# Main.net
KiCad netlist of a schematic drawn in Altium Designer
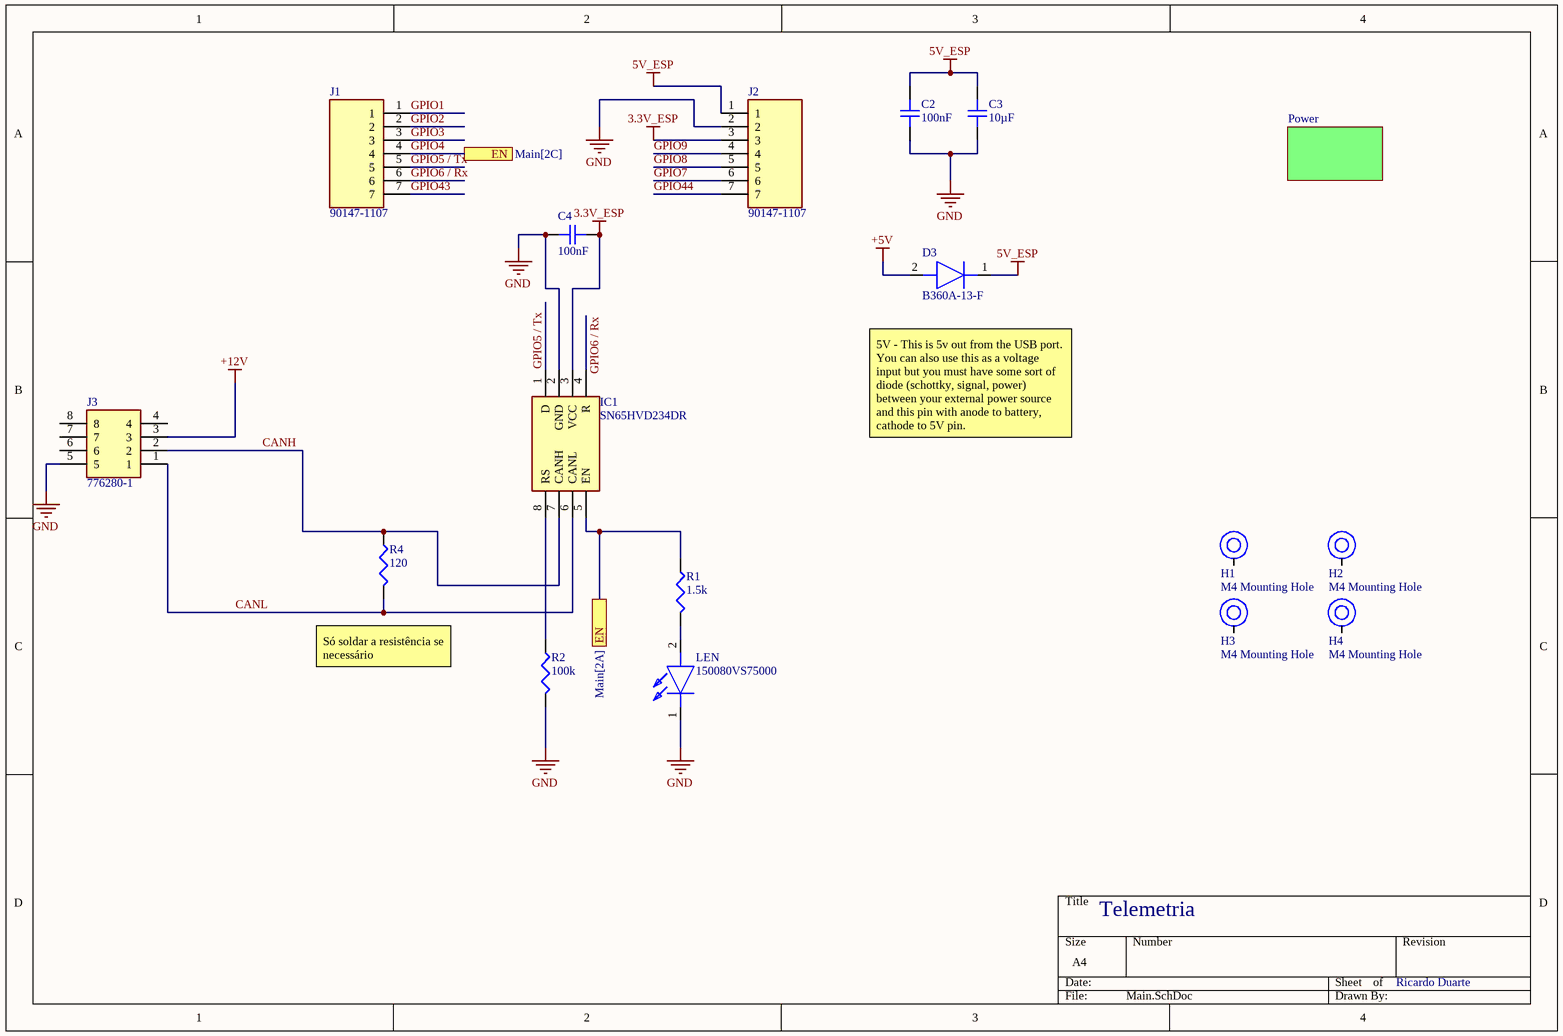
[diagram p0: Main.SchDoc]

(export (version "E")
  (design (tool "Eeschema 10.0.6"))
  (components
    (comp (ref "C2")
      (value "100nF")
      (footprint "CAP_0805")
      (fields (field (name "SOURCE") "Schematic-Lib-PhilsLab.SchLib"))
      (libsource (lib "EMEA- ISEL Formula Student-Instituto Superior Tecnico - Universidade de Lisboa") (part "100nF"))
    )
    (comp (ref "C3")
      (value "10µF")
      (footprint "CAP_0805")
      (fields (field (name "Comment") "10uF") (field (name "SOURCE") "Schematic-Lib-PhilsLab.SchLib"))
      (libsource (lib "EMEA- ISEL Formula Student-Instituto Superior Tecnico - Universidade de Lisboa") (part "10uF"))
    )
    (comp (ref "C4")
      (value "100nF")
      (footprint "CAP_0805")
      (fields (field (name "SOURCE") "Schematic-Lib-PhilsLab.SchLib"))
      (libsource (lib "EMEA- ISEL Formula Student-Instituto Superior Tecnico - Universidade de Lisboa") (part "100nF"))
    )
    (comp (ref "D3")
      (value "B360A-13-F")
      (footprint "FP-SMA-MFG")
      (description "Rectifier Diode, Schottky, 1 Phase, 1 Element, 3A, 60V V(RRM), Silicon")
      (fields (field (name "MOUSER PART NUMBER") "621-B360A-F"))
      (libsource (lib "EMEA- ISEL Formula Student-Instituto Superior Tecnico - Universidade de Lisboa") (part "B360A-13-F"))
    )
    (comp (ref "H1")
      (value "M4 Mounting Hole")
      (footprint "M4 Screw Hole-Footprint-1")
      (description "IFS Standard M4 hole for mounting PCBs")
      (libsource (lib "EMEA- ISEL Formula Student-Instituto Superior Tecnico - Universidade de Lisboa") (part "M4 Mounting  Hole"))
    )
    (comp (ref "H2")
      (value "M4 Mounting Hole")
      (footprint "M4 Screw Hole-Footprint-1")
      (description "IFS Standard M4 hole for mounting PCBs")
      (libsource (lib "EMEA- ISEL Formula Student-Instituto Superior Tecnico - Universidade de Lisboa") (part "M4 Mounting  Hole"))
    )
    (comp (ref "H3")
      (value "M4 Mounting Hole")
      (footprint "M4 Screw Hole-Footprint-1")
      (description "IFS Standard M4 hole for mounting PCBs")
      (libsource (lib "EMEA- ISEL Formula Student-Instituto Superior Tecnico - Universidade de Lisboa") (part "M4 Mounting  Hole"))
    )
    (comp (ref "H4")
      (value "M4 Mounting Hole")
      (footprint "M4 Screw Hole-Footprint-1")
      (description "IFS Standard M4 hole for mounting PCBs")
      (libsource (lib "EMEA- ISEL Formula Student-Instituto Superior Tecnico - Universidade de Lisboa") (part "M4 Mounting  Hole"))
    )
    (comp (ref "IC1")
      (value "SN65HVD234DR")
      (footprint "SamacSys:SOIC127P600X175-8N")
      (description "Integrated Circuit")
      (fields (field (name "MOUSER PART NUMBER") "595-SN65HVD234DR"))
      (libsource (lib "*") (part "SN65HVD234DR"))
    )
    (comp (ref "J1")
      (value "90147-1107")
      (footprint "SamacSys:SHDR7W65P0X254_1X7_2024X510X1180P")
      (description "Connector")
      (fields (field (name "MOUSER PART NUMBER") "538-90147-1107"))
      (libsource (lib "*") (part "90147-1107"))
    )
    (comp (ref "J2")
      (value "90147-1107")
      (footprint "SamacSys:SHDR7W65P0X254_1X7_2024X510X1180P")
      (description "Connector")
      (fields (field (name "MOUSER PART NUMBER") "538-90147-1107"))
      (libsource (lib "") (part "90147-1107_1"))
    )
    (comp (ref "J3")
      (value "776280-1")
      (footprint "776280-1")
      (description "Connector")
      (fields (field (name "MOUSER PART NUMBER") "571-776280-1"))
      (libsource (lib "EMEA- ISEL Formula Student-Instituto Superior Tecnico - Universidade de Lisboa") (part "776280-1"))
    )
    (comp (ref "LEN")
      (value "150080VS75000")
      (footprint "LEDC2012X80N")
      (description "Single Color LED, Bright Green, Water Clear, 1.4mm")
      (fields (field (name "MOUSER PART NUMBER") "710-150080VS75000"))
      (libsource (lib "EMEA- ISEL Formula Student-Instituto Superior Tecnico - Universidade de Lisboa") (part "150080VS75000"))
    )
    (comp (ref "R1")
      (value "1.5k")
      (footprint "RES_0805")
      (description "Resistor SMD 0805 4,7K")
      (fields (field (name "Comment") "4K7") (field (name "SOURCE") "Schematic-Lib-PhilsLab.SchLib"))
      (libsource (lib "EMEA- ISEL Formula Student-Instituto Superior Tecnico - Universidade de Lisboa") (part "RES_5931"))
    )
    (comp (ref "R2")
      (value "100k")
      (footprint "RES_0805")
      (description "Resistor SMD 0805 4,7K")
      (fields (field (name "Comment") "4K7") (field (name "SOURCE") "Schematic-Lib-PhilsLab.SchLib"))
      (libsource (lib "EMEA- ISEL Formula Student-Instituto Superior Tecnico - Universidade de Lisboa") (part "RES_5931"))
    )
    (comp (ref "R4")
      (value "120")
      (footprint "RES_0805")
      (description "Resistor SMD 0805 4,7K")
      (fields (field (name "Comment") "4K7") (field (name "SOURCE") "Schematic-Lib-PhilsLab.SchLib"))
      (libsource (lib "EMEA- ISEL Formula Student-Instituto Superior Tecnico - Universidade de Lisboa") (part "RES_5931"))
    )
  )
  (nets
    (net (code "1") (name "+5V") (class "Default")
      (node (ref "D3") (pin "2") (pinfunction "A_2") (pintype "passive"))
    )
    (net (code "2") (name "+12V") (class "Default")
      (node (ref "J3") (pin "3") (pinfunction "3_3") (pintype "passive"))
    )
    (net (code "3") (name "/CANH") (class "Default")
      (node (ref "IC1") (pin "7") (pinfunction "CANH_7") (pintype "passive"))
      (node (ref "J3") (pin "2") (pinfunction "2_2") (pintype "passive"))
      (node (ref "R4") (pin "1") (pinfunction "1_1") (pintype "passive"))
    )
    (net (code "4") (name "/CANL") (class "Default")
      (node (ref "IC1") (pin "6") (pinfunction "CANL_6") (pintype "passive"))
      (node (ref "J3") (pin "1") (pinfunction "1_1") (pintype "passive"))
      (node (ref "R4") (pin "2") (pinfunction "2_2") (pintype "passive"))
    )
    (net (code "5") (name "/GPIO1") (class "Default")
      (node (ref "J1") (pin "1") (pinfunction "1_1") (pintype "passive"))
    )
    (net (code "6") (name "/GPIO2") (class "Default")
      (node (ref "J1") (pin "2") (pinfunction "2_2") (pintype "passive"))
    )
    (net (code "7") (name "/GPIO3") (class "Default")
      (node (ref "J1") (pin "3") (pinfunction "3_3") (pintype "passive"))
    )
    (net (code "8") (name "/GPIO4") (class "Default")
      (node (ref "IC1") (pin "5") (pinfunction "EN_5") (pintype "passive"))
      (node (ref "J1") (pin "4") (pinfunction "4_4") (pintype "passive"))
      (node (ref "R1") (pin "1") (pinfunction "1_1") (pintype "passive"))
    )
    (net (code "9") (name "/GPIO5 {slash} Tx") (class "Default")
      (node (ref "IC1") (pin "1") (pinfunction "D_1") (pintype "passive"))
      (node (ref "J1") (pin "5") (pinfunction "5_5") (pintype "passive"))
    )
    (net (code "10") (name "/GPIO6 {slash} Rx") (class "Default")
      (node (ref "IC1") (pin "4") (pinfunction "R_4") (pintype "passive"))
      (node (ref "J1") (pin "6") (pinfunction "6_6") (pintype "passive"))
    )
    (net (code "11") (name "/GPIO7") (class "Default")
      (node (ref "J2") (pin "6") (pinfunction "6_6") (pintype "passive"))
    )
    (net (code "12") (name "/GPIO8") (class "Default")
      (node (ref "J2") (pin "5") (pinfunction "5_5") (pintype "passive"))
    )
    (net (code "13") (name "/GPIO9") (class "Default")
      (node (ref "J2") (pin "4") (pinfunction "4_4") (pintype "passive"))
    )
    (net (code "14") (name "/GPIO43") (class "Default")
      (node (ref "J1") (pin "7") (pinfunction "7_7") (pintype "passive"))
    )
    (net (code "15") (name "/GPIO44") (class "Default")
      (node (ref "J2") (pin "7") (pinfunction "7_7") (pintype "passive"))
    )
    (net (code "16") (name "3.3V_ESP") (class "Default")
      (node (ref "C4") (pin "2") (pinfunction "2_2") (pintype "passive"))
      (node (ref "IC1") (pin "3") (pinfunction "VCC_3") (pintype "passive"))
      (node (ref "J2") (pin "3") (pinfunction "3_3") (pintype "passive"))
    )
    (net (code "17") (name "5V_ESP") (class "Default")
      (node (ref "C2") (pin "2") (pinfunction "2_2") (pintype "passive"))
      (node (ref "C3") (pin "2") (pinfunction "2_2") (pintype "passive"))
      (node (ref "D3") (pin "1") (pinfunction "K_1") (pintype "passive"))
      (node (ref "J2") (pin "1") (pinfunction "1_1") (pintype "passive"))
    )
    (net (code "18") (name "GND") (class "Default")
      (node (ref "C2") (pin "1") (pinfunction "1_1") (pintype "passive"))
      (node (ref "C3") (pin "1") (pinfunction "1_1") (pintype "passive"))
      (node (ref "C4") (pin "1") (pinfunction "1_1") (pintype "passive"))
      (node (ref "IC1") (pin "2") (pinfunction "GND_2") (pintype "passive"))
      (node (ref "J2") (pin "2") (pinfunction "2_2") (pintype "passive"))
      (node (ref "J3") (pin "5") (pinfunction "5_5") (pintype "passive"))
      (node (ref "LEN") (pin "1") (pinfunction "K_1") (pintype "passive"))
      (node (ref "R2") (pin "2") (pinfunction "2_2") (pintype "passive"))
    )
    (net (code "19") (name "Net-(IC1-RS)") (class "Default")
      (node (ref "IC1") (pin "8") (pinfunction "RS_8") (pintype "passive"))
      (node (ref "R2") (pin "1") (pinfunction "1_1") (pintype "passive"))
    )
    (net (code "20") (name "Net-(LEN-A)") (class "Default")
      (node (ref "LEN") (pin "2") (pinfunction "A_2") (pintype "passive"))
      (node (ref "R1") (pin "2") (pinfunction "2_2") (pintype "passive"))
    )
    (net (code "21") (name "unconnected-(H1-Pad1)") (class "Default")
      (node (ref "H1") (pin "1") (pinfunction "1_1") (pintype "passive"))
    )
    (net (code "22") (name "unconnected-(H2-Pad1)") (class "Default")
      (node (ref "H2") (pin "1") (pinfunction "1_1") (pintype "passive"))
    )
    (net (code "23") (name "unconnected-(H3-Pad1)") (class "Default")
      (node (ref "H3") (pin "1") (pinfunction "1_1") (pintype "passive"))
    )
    (net (code "24") (name "unconnected-(H4-Pad1)") (class "Default")
      (node (ref "H4") (pin "1") (pinfunction "1_1") (pintype "passive"))
    )
    (net (code "25") (name "unconnected-(J3-Pad4)") (class "Default")
      (node (ref "J3") (pin "4") (pinfunction "4_4") (pintype "passive"))
    )
    (net (code "26") (name "unconnected-(J3-Pad6)") (class "Default")
      (node (ref "J3") (pin "6") (pinfunction "6_6") (pintype "passive"))
    )
    (net (code "27") (name "unconnected-(J3-Pad7)") (class "Default")
      (node (ref "J3") (pin "7") (pinfunction "7_7") (pintype "passive"))
    )
    (net (code "28") (name "unconnected-(J3-Pad8)") (class "Default")
      (node (ref "J3") (pin "8") (pinfunction "8_8") (pintype "passive"))
    )
  )
)
